# Button_Input_Card.net
KiCad netlist of a schematic drawn in EAGLE
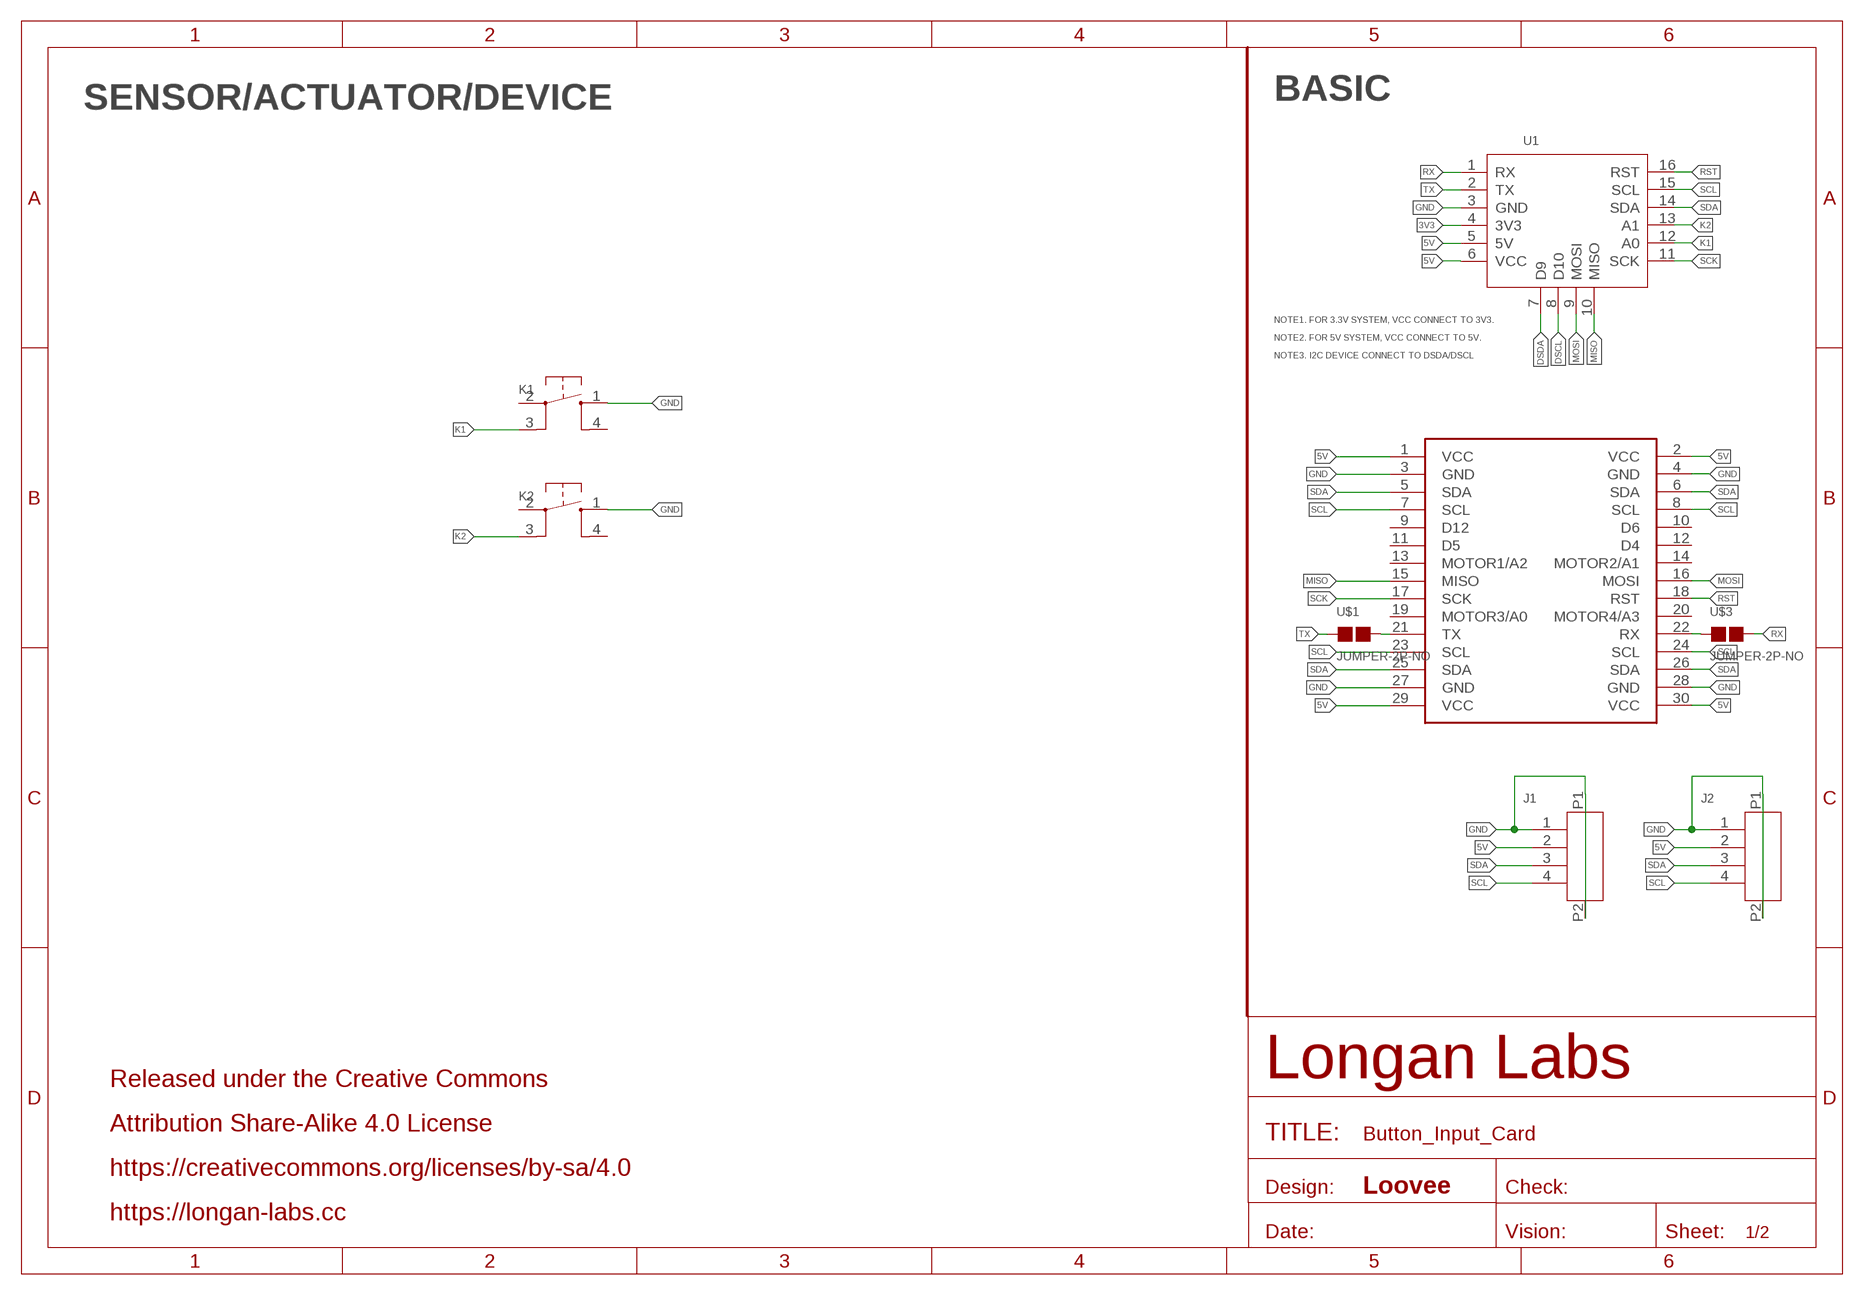
[diagram p0: schematic, sheet 1]

(export (version "E")
  (design (tool "Eeschema 10.0.6"))
  (components
    (comp (ref "J1")
      (value "HEADER-4P-1.0")
      (footprint "eagle-import:4P-1.0-90D")
      (libsource (lib "eagle-import") (part "HEADER-4P-1.0"))
    )
    (comp (ref "J2")
      (value "HEADER-4P-1.0")
      (footprint "eagle-import:4P-1.0-90D")
      (libsource (lib "eagle-import") (part "HEADER-4P-1.0"))
    )
    (comp (ref "K1")
      (value "BUTTON-4P-SMT-TS-1103CW")
      (footprint "eagle-import:SW4-SMD-5.0-12X12X7.5MM")
      (libsource (lib "eagle-import") (part "BUTTON-4P-SMT-TS-1103CW"))
    )
    (comp (ref "K2")
      (value "BUTTON-4P-SMT-TS-1103CW")
      (footprint "eagle-import:SW4-SMD-5.0-12X12X7.5MM")
      (libsource (lib "eagle-import") (part "BUTTON-4P-SMT-TS-1103CW"))
    )
    (comp (ref "MOUDLE1")
      (value "MOUDLE-2X15P-2.54'BOARD'")
      (footprint "eagle-import:MOUDLE-2X15P-2.54")
      (libsource (lib "eagle-import") (part "MOUDLE-2X15P-2.54'BOARD'"))
    )
    (comp (ref "U$1")
      (value "JUMPER-2P-NO")
      (footprint "eagle-import:2P-SMD-NO")
      (libsource (lib "eagle-import") (part "JUMPER-2P-NO"))
    )
    (comp (ref "U$3")
      (value "JUMPER-2P-NO")
      (footprint "eagle-import:2P-SMD-NO")
      (libsource (lib "eagle-import") (part "JUMPER-2P-NO"))
    )
    (comp (ref "U1")
      (value "MOUDLE-CARDS")
      (footprint "eagle-import:16P-2.0-CARDS")
      (libsource (lib "eagle-import") (part "MOUDLE-CARDS"))
    )
  )
  (nets
    (net (code "1") (name "3V3") (class "Default")
      (node (ref "U1") (pin "4") (pinfunction "3V3_4") (pintype "bidirectional"))
    )
    (net (code "2") (name "5V") (class "Default")
      (node (ref "J1") (pin "2") (pinfunction "2_2") (pintype "bidirectional"))
      (node (ref "J2") (pin "2") (pinfunction "2_2") (pintype "bidirectional"))
      (node (ref "MOUDLE1") (pin "1") (pinfunction "VCC_1") (pintype "bidirectional"))
      (node (ref "MOUDLE1") (pin "2") (pinfunction "VCC_2") (pintype "bidirectional"))
      (node (ref "MOUDLE1") (pin "29") (pinfunction "VCC_29") (pintype "bidirectional"))
      (node (ref "MOUDLE1") (pin "30") (pinfunction "VCC_30") (pintype "bidirectional"))
      (node (ref "U1") (pin "5") (pinfunction "5V_5") (pintype "bidirectional"))
      (node (ref "U1") (pin "6") (pinfunction "VCC_6") (pintype "bidirectional"))
    )
    (net (code "3") (name "DSCL") (class "Default")
      (node (ref "U1") (pin "8") (pinfunction "D10_8") (pintype "bidirectional"))
    )
    (net (code "4") (name "DSDA") (class "Default")
      (node (ref "U1") (pin "7") (pinfunction "D9_7") (pintype "bidirectional"))
    )
    (net (code "5") (name "GND") (class "Default")
      (node (ref "J1") (pin "1") (pinfunction "1_1") (pintype "bidirectional"))
      (node (ref "J1") (pin "P1") (pinfunction "P1_P1") (pintype "bidirectional"))
      (node (ref "J1") (pin "P2") (pinfunction "P2_P2") (pintype "bidirectional"))
      (node (ref "J2") (pin "1") (pinfunction "1_1") (pintype "bidirectional"))
      (node (ref "J2") (pin "P1") (pinfunction "P1_P1") (pintype "bidirectional"))
      (node (ref "J2") (pin "P2") (pinfunction "P2_P2") (pintype "bidirectional"))
      (node (ref "K1") (pin "1") (pinfunction "1_1") (pintype "bidirectional"))
      (node (ref "K2") (pin "1") (pinfunction "1_1") (pintype "bidirectional"))
      (node (ref "MOUDLE1") (pin "27") (pinfunction "GND_27") (pintype "bidirectional"))
      (node (ref "MOUDLE1") (pin "28") (pinfunction "GND_28") (pintype "bidirectional"))
      (node (ref "MOUDLE1") (pin "3") (pinfunction "GND_3") (pintype "bidirectional"))
      (node (ref "MOUDLE1") (pin "4") (pinfunction "GND_4") (pintype "bidirectional"))
      (node (ref "U1") (pin "3") (pinfunction "GND_3") (pintype "bidirectional"))
    )
    (net (code "6") (name "K1") (class "Default")
      (node (ref "K1") (pin "3") (pinfunction "3_3") (pintype "bidirectional"))
      (node (ref "U1") (pin "12") (pinfunction "A0_12") (pintype "bidirectional"))
    )
    (net (code "7") (name "K2") (class "Default")
      (node (ref "K2") (pin "3") (pinfunction "3_3") (pintype "bidirectional"))
      (node (ref "U1") (pin "13") (pinfunction "A1_13") (pintype "bidirectional"))
    )
    (net (code "8") (name "MISO") (class "Default")
      (node (ref "MOUDLE1") (pin "15") (pinfunction "MISO_15") (pintype "bidirectional"))
      (node (ref "U1") (pin "10") (pinfunction "MISO_10") (pintype "bidirectional"))
    )
    (net (code "9") (name "MOSI") (class "Default")
      (node (ref "MOUDLE1") (pin "16") (pinfunction "MOSI_16") (pintype "bidirectional"))
      (node (ref "U1") (pin "9") (pinfunction "MOSI_9") (pintype "bidirectional"))
    )
    (net (code "10") (name "Net-(MOUDLE1-RX)") (class "Default")
      (node (ref "MOUDLE1") (pin "22") (pinfunction "RX_22") (pintype "bidirectional"))
      (node (ref "U$3") (pin "1") (pinfunction "1_1") (pintype "bidirectional"))
    )
    (net (code "11") (name "Net-(MOUDLE1-TX)") (class "Default")
      (node (ref "MOUDLE1") (pin "21") (pinfunction "TX_21") (pintype "bidirectional"))
      (node (ref "U$1") (pin "2") (pinfunction "2_2") (pintype "bidirectional"))
    )
    (net (code "12") (name "RST") (class "Default")
      (node (ref "MOUDLE1") (pin "18") (pinfunction "RST_18") (pintype "bidirectional"))
      (node (ref "U1") (pin "16") (pinfunction "RST_16") (pintype "bidirectional"))
    )
    (net (code "13") (name "RX") (class "Default")
      (node (ref "U$3") (pin "2") (pinfunction "2_2") (pintype "bidirectional"))
      (node (ref "U1") (pin "1") (pinfunction "RX_1") (pintype "bidirectional"))
    )
    (net (code "14") (name "SCK") (class "Default")
      (node (ref "MOUDLE1") (pin "17") (pinfunction "SCK_17") (pintype "bidirectional"))
      (node (ref "U1") (pin "11") (pinfunction "SCK_11") (pintype "bidirectional"))
    )
    (net (code "15") (name "SCL") (class "Default")
      (node (ref "J1") (pin "4") (pinfunction "4_4") (pintype "bidirectional"))
      (node (ref "J2") (pin "4") (pinfunction "4_4") (pintype "bidirectional"))
      (node (ref "MOUDLE1") (pin "23") (pinfunction "SCL_23") (pintype "bidirectional"))
      (node (ref "MOUDLE1") (pin "24") (pinfunction "SCL_24") (pintype "bidirectional"))
      (node (ref "MOUDLE1") (pin "7") (pinfunction "SCL_7") (pintype "bidirectional"))
      (node (ref "MOUDLE1") (pin "8") (pinfunction "SCL_8") (pintype "bidirectional"))
      (node (ref "U1") (pin "15") (pinfunction "SCL_15") (pintype "bidirectional"))
    )
    (net (code "16") (name "SDA") (class "Default")
      (node (ref "J1") (pin "3") (pinfunction "3_3") (pintype "bidirectional"))
      (node (ref "J2") (pin "3") (pinfunction "3_3") (pintype "bidirectional"))
      (node (ref "MOUDLE1") (pin "25") (pinfunction "SDA_25") (pintype "bidirectional"))
      (node (ref "MOUDLE1") (pin "26") (pinfunction "SDA_26") (pintype "bidirectional"))
      (node (ref "MOUDLE1") (pin "5") (pinfunction "SDA_5") (pintype "bidirectional"))
      (node (ref "MOUDLE1") (pin "6") (pinfunction "SDA_6") (pintype "bidirectional"))
      (node (ref "U1") (pin "14") (pinfunction "SDA_14") (pintype "bidirectional"))
    )
    (net (code "17") (name "TX") (class "Default")
      (node (ref "U$1") (pin "1") (pinfunction "1_1") (pintype "bidirectional"))
      (node (ref "U1") (pin "2") (pinfunction "TX_2") (pintype "bidirectional"))
    )
    (net (code "18") (name "unconnected-(K1-Pad2)") (class "Default")
      (node (ref "K1") (pin "2") (pinfunction "2_2") (pintype "bidirectional"))
    )
    (net (code "19") (name "unconnected-(K1-Pad4)") (class "Default")
      (node (ref "K1") (pin "4") (pinfunction "4_4") (pintype "bidirectional"))
    )
    (net (code "20") (name "unconnected-(K2-Pad2)") (class "Default")
      (node (ref "K2") (pin "2") (pinfunction "2_2") (pintype "bidirectional"))
    )
    (net (code "21") (name "unconnected-(K2-Pad4)") (class "Default")
      (node (ref "K2") (pin "4") (pinfunction "4_4") (pintype "bidirectional"))
    )
    (net (code "22") (name "unconnected-(MOUDLE1-D4-Pad12)") (class "Default")
      (node (ref "MOUDLE1") (pin "12") (pinfunction "D4_12") (pintype "bidirectional"))
    )
    (net (code "23") (name "unconnected-(MOUDLE1-D5-Pad11)") (class "Default")
      (node (ref "MOUDLE1") (pin "11") (pinfunction "D5_11") (pintype "bidirectional"))
    )
    (net (code "24") (name "unconnected-(MOUDLE1-D6-Pad10)") (class "Default")
      (node (ref "MOUDLE1") (pin "10") (pinfunction "D6_10") (pintype "bidirectional"))
    )
    (net (code "25") (name "unconnected-(MOUDLE1-D12-Pad9)") (class "Default")
      (node (ref "MOUDLE1") (pin "9") (pinfunction "D12_9") (pintype "bidirectional"))
    )
    (net (code "26") (name "unconnected-(MOUDLE1-MOTOR1{slash}A2-Pad13)") (class "Default")
      (node (ref "MOUDLE1") (pin "13") (pinfunction "MOTOR1/A2_13") (pintype "bidirectional"))
    )
    (net (code "27") (name "unconnected-(MOUDLE1-MOTOR2{slash}A1-Pad14)") (class "Default")
      (node (ref "MOUDLE1") (pin "14") (pinfunction "MOTOR2/A1_14") (pintype "bidirectional"))
    )
    (net (code "28") (name "unconnected-(MOUDLE1-MOTOR3{slash}A0-Pad19)") (class "Default")
      (node (ref "MOUDLE1") (pin "19") (pinfunction "MOTOR3/A0_19") (pintype "bidirectional"))
    )
    (net (code "29") (name "unconnected-(MOUDLE1-MOTOR4{slash}A3-Pad20)") (class "Default")
      (node (ref "MOUDLE1") (pin "20") (pinfunction "MOTOR4/A3_20") (pintype "bidirectional"))
    )
  )
)
